# Booster_USER_IFC_W5500.net
KiCad netlist of a schematic drawn in Altium Designer
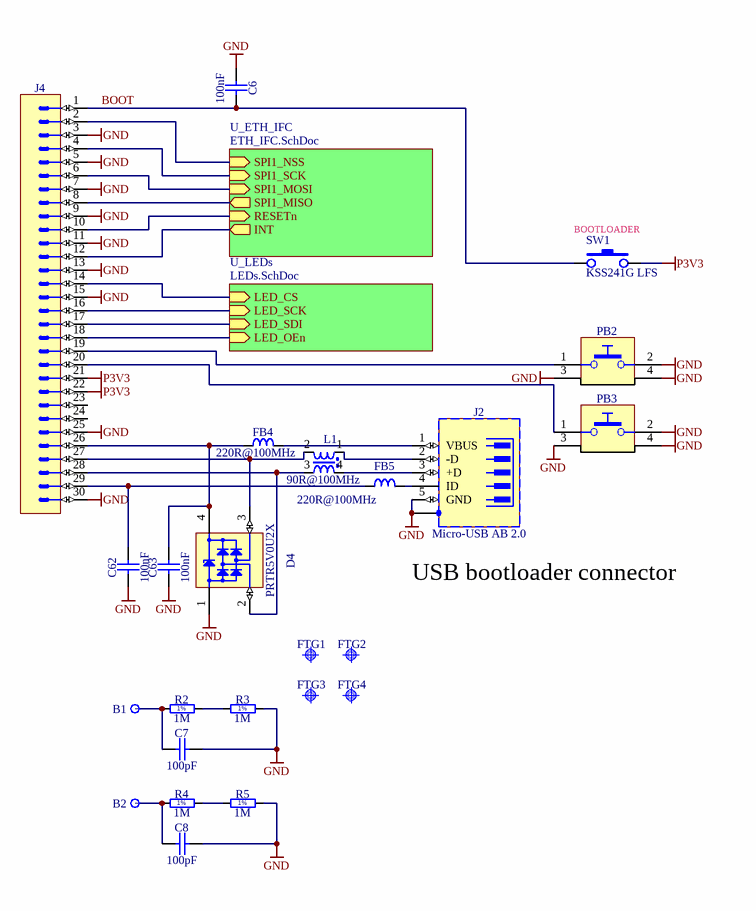
[diagram p0: Booster_USER_IFC_W5500.SchDoc]

(export (version "E")
  (design (tool "Eeschema 10.0.6"))
  (components
    (comp (ref "B1")
      (value "Plated Hole")
      (footprint "MTG320_550")
      (description "Single Terminal Socket")
      (fields (field (name "PART NUMBER") "PLATED_HOLE3.2_PAD5.5") (field (name "AUTHOR") "CERN DEM JMW"))
      (libsource (lib "Eletro-mechanical") (part "Single Terminal Socket"))
    )
    (comp (ref "B2")
      (value "Plated Hole")
      (footprint "MTG320_550")
      (description "Single Terminal Socket")
      (fields (field (name "PART NUMBER") "PLATED_HOLE3.2_PAD5.5") (field (name "AUTHOR") "CERN DEM JMW"))
      (libsource (lib "Eletro-mechanical") (part "Single Terminal Socket"))
    )
    (comp (ref "C6")
      (value "100nF")
      (footprint "CAPC1005X55N")
      (description "Non-polarised capacitor")
      (fields
        (field (name "PART NUMBER") "CC0402_100NF_16V_10%_X7R")
        (field (name "VOLTAGE") "16V")
        (field (name "AUTHOR") "CERN DEM JLC")
      )
      (libsource (lib "Capacitors") (part "Capacitor - non polarized"))
    )
    (comp (ref "C7")
      (value "100pF")
      (footprint "CAPC2012X88N")
      (description "Non-polarised capacitor")
      (fields
        (field (name "PART NUMBER") "CC0805_100PF_200V_5%_C0G")
        (field (name "VOLTAGE") "200V")
        (field (name "AUTHOR") "CERN DEM JLC")
      )
      (libsource (lib "Capacitors") (part "Capacitor - non polarized"))
    )
    (comp (ref "C8")
      (value "100pF")
      (footprint "CAPC2012X88N")
      (description "Non-polarised capacitor")
      (fields
        (field (name "PART NUMBER") "CC0805_100PF_200V_5%_C0G")
        (field (name "VOLTAGE") "200V")
        (field (name "AUTHOR") "CERN DEM JLC")
      )
      (libsource (lib "Capacitors") (part "Capacitor - non polarized"))
    )
    (comp (ref "C62")
      (value "100nF")
      (footprint "CAPC1005X55N")
      (description "Non-polarised capacitor")
      (fields
        (field (name "PART NUMBER") "CC0402_100NF_16V_10%_X7R")
        (field (name "VOLTAGE") "16V")
        (field (name "AUTHOR") "CERN DEM JLC")
      )
      (libsource (lib "Capacitors") (part "Capacitor - non polarized"))
    )
    (comp (ref "C63")
      (value "100nF")
      (footprint "CAPC1005X55N")
      (description "Non-polarised capacitor")
      (fields
        (field (name "PART NUMBER") "CC0402_100NF_16V_10%_X7R")
        (field (name "VOLTAGE") "16V")
        (field (name "AUTHOR") "CERN DEM JLC")
      )
      (libsource (lib "Capacitors") (part "Capacitor - non polarized"))
    )
    (comp (ref "D4")
      (value "PRTR5V0U2X")
      (footprint "SOT190P230X110-4N")
      (description "Ultra Low Capacitance Double Rail-to-Rail ESD Protection Diode")
      (fields
        (field (name "VOLTAGE") "5.5V")
        (field (name "MANUFACTURER") "NXP SEMICONDUCTORS")
        (field (name "AUTHOR") "CERN DEM JLC")
      )
      (libsource (lib "ICs And Semiconductors") (part "PRTR5V0U2X"))
    )
    (comp (ref "FB4")
      (value "220R@100MHz")
      (footprint "INDC2012X105N")
      (description "Inductor")
      (fields
        (field (name "PART NUMBER") "IND0805_MURATA_BLM21PG221SN1D")
        (field (name "POWER") "2A")
        (field (name "AUTHOR") "CERN DEM JLC")
      )
      (libsource (lib "Inductors & Transformers") (part "Inductor"))
    )
    (comp (ref "FB5")
      (value "220R@100MHz")
      (footprint "INDC2012X105N")
      (description "Inductor")
      (fields
        (field (name "PART NUMBER") "IND0805_MURATA_BLM21PG221SN1D")
        (field (name "POWER") "2A")
        (field (name "AUTHOR") "CERN DEM JLC")
      )
      (libsource (lib "Inductors & Transformers") (part "Inductor"))
    )
    (comp (ref "FTG1")
      (value "Use only in PCB")
      (footprint "FIDUCIAL_TOP_C100-200")
      (description "Fiducial Target")
      (fields (field (name "PART NUMBER") "FIDUCIAL_TARGET_C100-200") (field (name "AUTHOR") "CERN DEM JLC"))
      (libsource (lib "Eletro-mechanical") (part "Fiducial Target"))
    )
    (comp (ref "FTG2")
      (value "Use only in PCB")
      (footprint "FIDUCIAL_TOP_C100-200")
      (description "Fiducial Target")
      (fields (field (name "PART NUMBER") "FIDUCIAL_TARGET_C100-200") (field (name "AUTHOR") "CERN DEM JLC"))
      (libsource (lib "Eletro-mechanical") (part "Fiducial Target"))
    )
    (comp (ref "FTG3")
      (value "Use only in PCB")
      (footprint "FIDUCIAL_TOP_S100-200")
      (description "Fiducial Target")
      (fields (field (name "PART NUMBER") "FIDUCIAL_TARGET_S100-200") (field (name "AUTHOR") "CERN DEM JLC"))
      (libsource (lib "Eletro-mechanical") (part "Fiducial Target"))
    )
    (comp (ref "FTG4")
      (value "Use only in PCB")
      (footprint "FIDUCIAL_TOP_S100-200")
      (description "Fiducial Target")
      (fields (field (name "PART NUMBER") "FIDUCIAL_TARGET_S100-200") (field (name "AUTHOR") "CERN DEM JLC"))
      (libsource (lib "Eletro-mechanical") (part "Fiducial Target"))
    )
    (comp (ref "J2")
      (value "Micro-USB AB 2.0")
      (footprint "HIROSE_ZX62RD-AB-5P8")
      (description "5 Pin + 1 Shield USB Receptacle")
      (fields
        (field (name "PART NUMBER") "HIROSE_ZX62RD-AB-5P8")
        (field (name "MANUFACTURER") "HIROSE (HRS)")
        (field (name "AUTHOR") "CERN DEM JLC")
      )
      (libsource (lib "Connectors") (part "Connector USB 5 Pin + 1Shield"))
    )
    (comp (ref "J4")
      (value "~")
      (footprint "3M_N2530-6002RB")
      (description "Connector 30 Male")
      (fields
        (field (name "PART NUMBER") "3M_N2530-6002RB")
        (field (name "MANUFACTURER") "3M")
        (field (name "AUTHOR") "CERN DEM JLC")
      )
      (libsource (lib "Connectors") (part "Connector 30 Male"))
    )
    (comp (ref "L1")
      (value "90R@100MHz")
      (footprint "IND_MURATA_DLW21S")
      (description "Inductor Common Mode")
      (fields
        (field (name "PART NUMBER") "IND_MURATA_DLW21SN900SQ2L")
        (field (name "POWER") "330mA")
        (field (name "AUTHOR") "CERN DEM JLC")
      )
      (libsource (lib "Inductors & Transformers") (part "Inductor Common Mode 1Dot-2 4Dot-3"))
    )
    (comp (ref "PB2")
      (value "Push Button")
      (footprint "PB_TYCO_1-1825027-1")
      (description "Push-Button Switch SPDT")
      (fields
        (field (name "PART NUMBER") "PB_TYCO_1-1825027-1")
        (field (name "MANUFACTURER") "TYCO ELECTRONICS")
        (field (name "AUTHOR") "CERN DEM JLC")
      )
      (libsource (lib "Eletro-mechanical") (part "PB SPST 1NO-2NO 34CASE"))
    )
    (comp (ref "PB3")
      (value "Push Button")
      (footprint "PB_TYCO_1-1825027-1")
      (description "Push-Button Switch SPDT")
      (fields
        (field (name "PART NUMBER") "PB_TYCO_1-1825027-1")
        (field (name "MANUFACTURER") "TYCO ELECTRONICS")
        (field (name "AUTHOR") "CERN DEM JLC")
      )
      (libsource (lib "Eletro-mechanical") (part "PB SPST 1NO-2NO 34CASE"))
    )
    (comp (ref "R2")
      (value "1M")
      (footprint "RESC1005X40N")
      (description "Resistor - 1%")
      (fields
        (field (name "PART NUMBER") "R0402_1M_1%_0.0625W_100PPM")
        (field (name "POWER") "0.0625W")
        (field (name "AUTHOR") "CERN DEM JLC")
      )
      (libsource (lib "Resistors") (part "Resistor - 1%"))
    )
    (comp (ref "R3")
      (value "1M")
      (footprint "RESC1005X40N")
      (description "Resistor - 1%")
      (fields
        (field (name "PART NUMBER") "R0402_1M_1%_0.0625W_100PPM")
        (field (name "POWER") "0.0625W")
        (field (name "AUTHOR") "CERN DEM JLC")
      )
      (libsource (lib "Resistors") (part "Resistor - 1%"))
    )
    (comp (ref "R4")
      (value "1M")
      (footprint "RESC1005X40N")
      (description "Resistor - 1%")
      (fields
        (field (name "PART NUMBER") "R0402_1M_1%_0.0625W_100PPM")
        (field (name "POWER") "0.0625W")
        (field (name "AUTHOR") "CERN DEM JLC")
      )
      (libsource (lib "Resistors") (part "Resistor - 1%"))
    )
    (comp (ref "R5")
      (value "1M")
      (footprint "RESC1005X40N")
      (description "Resistor - 1%")
      (fields
        (field (name "PART NUMBER") "R0402_1M_1%_0.0625W_100PPM")
        (field (name "POWER") "0.0625W")
        (field (name "AUTHOR") "CERN DEM JLC")
      )
      (libsource (lib "Resistors") (part "Resistor - 1%"))
    )
    (comp (ref "SW1")
      (value "KSS241G LFS")
      (footprint "KSS241G LFS")
      (description "Push button")
      (libsource (lib "LIBRARY_SCH") (part "SW-TACT_SMD_RA_mini"))
    )
  )
  (nets
    (net (code "1") (name "/BOOT") (class "Default")
      (node (ref "C6") (pin "2") (pinfunction "2_2") (pintype "passive"))
      (node (ref "J4") (pin "1") (pinfunction "1_1") (pintype "bidirectional"))
      (node (ref "SW1") (pin "1") (pinfunction "1_1") (pintype "passive"))
    )
    (net (code "2") (name "/INT") (class "Default")
      (node (ref "J4") (pin "12") (pinfunction "12_12") (pintype "bidirectional"))
    )
    (net (code "3") (name "/LED_CS") (class "Default")
      (node (ref "J4") (pin "14") (pinfunction "14_14") (pintype "bidirectional"))
    )
    (net (code "4") (name "/LED_OEn") (class "Default")
      (node (ref "J4") (pin "18") (pinfunction "18_18") (pintype "bidirectional"))
    )
    (net (code "5") (name "/LED_SCK") (class "Default")
      (node (ref "J4") (pin "16") (pinfunction "16_16") (pintype "bidirectional"))
    )
    (net (code "6") (name "/LED_SDI") (class "Default")
      (node (ref "J4") (pin "17") (pinfunction "17_17") (pintype "bidirectional"))
    )
    (net (code "7") (name "/RESETn") (class "Default")
      (node (ref "J4") (pin "10") (pinfunction "10_10") (pintype "bidirectional"))
    )
    (net (code "8") (name "/SPI1_MISO") (class "Default")
      (node (ref "J4") (pin "8") (pinfunction "8_8") (pintype "bidirectional"))
    )
    (net (code "9") (name "/SPI1_MOSI") (class "Default")
      (node (ref "J4") (pin "6") (pinfunction "6_6") (pintype "bidirectional"))
    )
    (net (code "10") (name "/SPI1_NSS") (class "Default")
      (node (ref "J4") (pin "2") (pinfunction "2_2") (pintype "bidirectional"))
    )
    (net (code "11") (name "/SPI1_SCK") (class "Default")
      (node (ref "J4") (pin "4") (pinfunction "4_4") (pintype "bidirectional"))
    )
    (net (code "12") (name "GND") (class "Default")
      (node (ref "C6") (pin "1") (pinfunction "1_1") (pintype "passive"))
      (node (ref "C62") (pin "1") (pinfunction "1_1") (pintype "passive"))
      (node (ref "C63") (pin "1") (pinfunction "1_1") (pintype "passive"))
      (node (ref "C7") (pin "2") (pinfunction "2_2") (pintype "passive"))
      (node (ref "C8") (pin "2") (pinfunction "2_2") (pintype "passive"))
      (node (ref "D4") (pin "1") (pinfunction "GND_1") (pintype "power_in"))
      (node (ref "J2") (pin "5") (pinfunction "GND_5") (pintype "bidirectional"))
      (node (ref "J2") (pin "6") (pinfunction "SH_6") (pintype "power_in"))
      (node (ref "J4") (pin "11") (pinfunction "11_11") (pintype "bidirectional"))
      (node (ref "J4") (pin "13") (pinfunction "13_13") (pintype "bidirectional"))
      (node (ref "J4") (pin "15") (pinfunction "15_15") (pintype "bidirectional"))
      (node (ref "J4") (pin "25") (pinfunction "25_25") (pintype "bidirectional"))
      (node (ref "J4") (pin "3") (pinfunction "3_3") (pintype "bidirectional"))
      (node (ref "J4") (pin "30") (pinfunction "30_30") (pintype "bidirectional"))
      (node (ref "J4") (pin "5") (pinfunction "5_5") (pintype "bidirectional"))
      (node (ref "J4") (pin "7") (pinfunction "7_7") (pintype "bidirectional"))
      (node (ref "J4") (pin "9") (pinfunction "9_9") (pintype "bidirectional"))
      (node (ref "PB2") (pin "2") (pinfunction "2_2") (pintype "passive"))
      (node (ref "PB2") (pin "3") (pinfunction "3_3") (pintype "passive"))
      (node (ref "PB2") (pin "4") (pinfunction "4_4") (pintype "passive"))
      (node (ref "PB3") (pin "2") (pinfunction "2_2") (pintype "passive"))
      (node (ref "PB3") (pin "3") (pinfunction "3_3") (pintype "passive"))
      (node (ref "PB3") (pin "4") (pinfunction "4_4") (pintype "passive"))
      (node (ref "R3") (pin "2") (pinfunction "2_2") (pintype "passive"))
      (node (ref "R5") (pin "2") (pinfunction "2_2") (pintype "passive"))
    )
    (net (code "13") (name "Net-(B1-Pad1)") (class "Default")
      (node (ref "B1") (pin "1") (pinfunction "1_1") (pintype "bidirectional"))
      (node (ref "C7") (pin "1") (pinfunction "1_1") (pintype "passive"))
      (node (ref "R2") (pin "1") (pinfunction "1_1") (pintype "passive"))
    )
    (net (code "14") (name "Net-(B2-Pad1)") (class "Default")
      (node (ref "B2") (pin "1") (pinfunction "1_1") (pintype "bidirectional"))
      (node (ref "C8") (pin "1") (pinfunction "1_1") (pintype "passive"))
      (node (ref "R4") (pin "1") (pinfunction "1_1") (pintype "passive"))
    )
    (net (code "15") (name "Net-(C62-Pad2)") (class "Default")
      (node (ref "C62") (pin "2") (pinfunction "2_2") (pintype "passive"))
      (node (ref "FB5") (pin "1") (pinfunction "1_1") (pintype "passive"))
      (node (ref "J4") (pin "29") (pinfunction "29_29") (pintype "bidirectional"))
    )
    (net (code "16") (name "Net-(D4-I{slash}O1)") (class "Default")
      (node (ref "D4") (pin "2") (pinfunction "I/O1_2") (pintype "bidirectional"))
      (node (ref "J4") (pin "28") (pinfunction "28_28") (pintype "bidirectional"))
      (node (ref "L1") (pin "3") (pinfunction "3_3") (pintype "passive"))
    )
    (net (code "17") (name "Net-(D4-I{slash}O2)") (class "Default")
      (node (ref "D4") (pin "3") (pinfunction "I/O2_3") (pintype "bidirectional"))
      (node (ref "J4") (pin "27") (pinfunction "27_27") (pintype "bidirectional"))
      (node (ref "L1") (pin "2") (pinfunction "2_2") (pintype "passive"))
    )
    (net (code "18") (name "Net-(D4-VCC)") (class "Default")
      (node (ref "C63") (pin "2") (pinfunction "2_2") (pintype "passive"))
      (node (ref "D4") (pin "4") (pinfunction "VCC_4") (pintype "power_in"))
      (node (ref "FB4") (pin "1") (pinfunction "1_1") (pintype "passive"))
      (node (ref "J4") (pin "26") (pinfunction "26_26") (pintype "bidirectional"))
    )
    (net (code "19") (name "Net-(J2-+D)") (class "Default")
      (node (ref "J2") (pin "3") (pinfunction "+D_3") (pintype "bidirectional"))
      (node (ref "L1") (pin "4") (pinfunction "4_4") (pintype "passive"))
    )
    (net (code "20") (name "Net-(J2--D)") (class "Default")
      (node (ref "J2") (pin "2") (pinfunction "-D_2") (pintype "bidirectional"))
      (node (ref "L1") (pin "1") (pinfunction "1_1") (pintype "passive"))
    )
    (net (code "21") (name "Net-(J2-ID)") (class "Default")
      (node (ref "FB5") (pin "2") (pinfunction "2_2") (pintype "passive"))
      (node (ref "J2") (pin "4") (pinfunction "ID_4") (pintype "passive"))
    )
    (net (code "22") (name "Net-(J2-VBUS)") (class "Default")
      (node (ref "FB4") (pin "2") (pinfunction "2_2") (pintype "passive"))
      (node (ref "J2") (pin "1") (pinfunction "VBUS_1") (pintype "bidirectional"))
    )
    (net (code "23") (name "Net-(J4-Pad19)") (class "Default")
      (node (ref "J4") (pin "19") (pinfunction "19_19") (pintype "bidirectional"))
      (node (ref "PB2") (pin "1") (pinfunction "1_1") (pintype "passive"))
    )
    (net (code "24") (name "Net-(J4-Pad20)") (class "Default")
      (node (ref "J4") (pin "20") (pinfunction "20_20") (pintype "bidirectional"))
      (node (ref "PB3") (pin "1") (pinfunction "1_1") (pintype "passive"))
    )
    (net (code "25") (name "Net-(R2-Pad2)") (class "Default")
      (node (ref "R2") (pin "2") (pinfunction "2_2") (pintype "passive"))
      (node (ref "R3") (pin "1") (pinfunction "1_1") (pintype "passive"))
    )
    (net (code "26") (name "Net-(R4-Pad2)") (class "Default")
      (node (ref "R4") (pin "2") (pinfunction "2_2") (pintype "passive"))
      (node (ref "R5") (pin "1") (pinfunction "1_1") (pintype "passive"))
    )
    (net (code "27") (name "P3V3") (class "Default")
      (node (ref "J4") (pin "21") (pinfunction "21_21") (pintype "bidirectional"))
      (node (ref "J4") (pin "22") (pinfunction "22_22") (pintype "bidirectional"))
      (node (ref "SW1") (pin "2") (pinfunction "2_2") (pintype "passive"))
    )
    (net (code "28") (name "unconnected-(J4-Pad23)") (class "Default")
      (node (ref "J4") (pin "23") (pinfunction "23_23") (pintype "bidirectional"))
    )
    (net (code "29") (name "unconnected-(J4-Pad24)") (class "Default")
      (node (ref "J4") (pin "24") (pinfunction "24_24") (pintype "bidirectional"))
    )
  )
)
